# Thermistors.net
KiCad netlist of a schematic drawn in Altium Designer
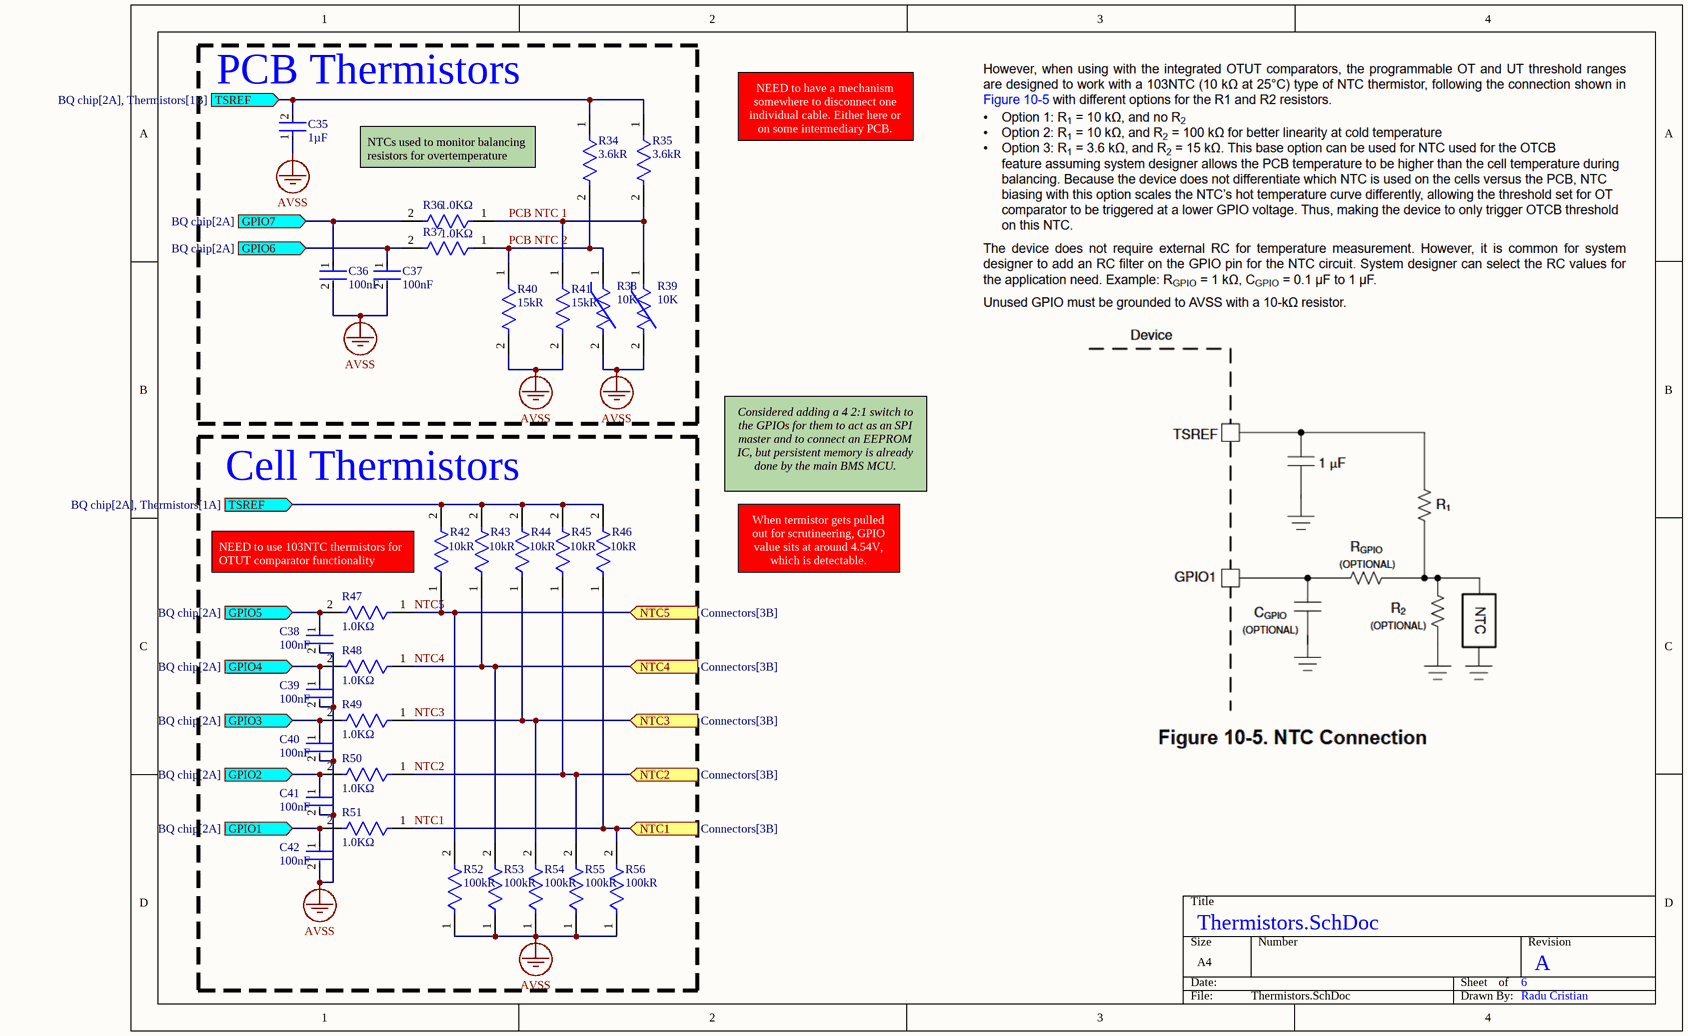
[diagram p0: Thermistors.SchDoc]

(export (version "E")
  (design (tool "Eeschema 10.0.6"))
  (components
    (comp (ref "C35")
      (value "VJ0603Y105KXJCW1BC")
      (footprint "FP-VJ0603Y105KXJCW1BC-MFG")
      (description "VJ0603Y105KXJCW1BC Multilayer Ceramic Capacitor, 1 uF, 16 V, ± 10%, X7R, 0603 [1608 Metric]")
      (fields (field (name "CAPACITANCE") "1µF") (field (name "TOLERANCE") "10%"))
      (libsource (lib "Altium Content Vault") (part "b4654b650e69147ec39a6b967a45e02"))
    )
    (comp (ref "C36")
      (value "GRM188R72A104MA35D")
      (footprint "FP-GRM188-0_1-e0_2_0_5-MFG")
      (description "Chip Multilayer Ceramic Capacitors for General Purpose, 0603, 0.10uF, X7R, 15%, 20%, 100V")
      (fields (field (name "CAPACITANCE") "100nF") (field (name "TOLERANCE") "20%"))
      (libsource (lib "Altium Content Vault") (part "11868f565c42a9108669ba33697ecf6"))
    )
    (comp (ref "C37")
      (value "GRM188R72A104MA35D")
      (footprint "FP-GRM188-0_1-e0_2_0_5-MFG")
      (description "Chip Multilayer Ceramic Capacitors for General Purpose, 0603, 0.10uF, X7R, 15%, 20%, 100V")
      (fields (field (name "CAPACITANCE") "100nF") (field (name "TOLERANCE") "20%"))
      (libsource (lib "Altium Content Vault") (part "11868f565c42a9108669ba33697ecf6"))
    )
    (comp (ref "C38")
      (value "GRM188R72A104MA35D")
      (footprint "FP-GRM188-0_1-e0_2_0_5-MFG")
      (description "Chip Multilayer Ceramic Capacitors for General Purpose, 0603, 0.10uF, X7R, 15%, 20%, 100V")
      (fields (field (name "CAPACITANCE") "100nF") (field (name "TOLERANCE") "20%"))
      (libsource (lib "Altium Content Vault") (part "11868f565c42a9108669ba33697ecf6"))
    )
    (comp (ref "C39")
      (value "GRM188R72A104MA35D")
      (footprint "FP-GRM188-0_1-e0_2_0_5-MFG")
      (description "Chip Multilayer Ceramic Capacitors for General Purpose, 0603, 0.10uF, X7R, 15%, 20%, 100V")
      (fields (field (name "CAPACITANCE") "100nF") (field (name "TOLERANCE") "20%"))
      (libsource (lib "Altium Content Vault") (part "11868f565c42a9108669ba33697ecf6"))
    )
    (comp (ref "C40")
      (value "GRM188R72A104MA35D")
      (footprint "FP-GRM188-0_1-e0_2_0_5-MFG")
      (description "Chip Multilayer Ceramic Capacitors for General Purpose, 0603, 0.10uF, X7R, 15%, 20%, 100V")
      (fields (field (name "CAPACITANCE") "100nF") (field (name "TOLERANCE") "20%"))
      (libsource (lib "Altium Content Vault") (part "11868f565c42a9108669ba33697ecf6"))
    )
    (comp (ref "C41")
      (value "GRM188R72A104MA35D")
      (footprint "FP-GRM188-0_1-e0_2_0_5-MFG")
      (description "Chip Multilayer Ceramic Capacitors for General Purpose, 0603, 0.10uF, X7R, 15%, 20%, 100V")
      (fields (field (name "CAPACITANCE") "100nF") (field (name "TOLERANCE") "20%"))
      (libsource (lib "Altium Content Vault") (part "11868f565c42a9108669ba33697ecf6"))
    )
    (comp (ref "C42")
      (value "GRM188R72A104MA35D")
      (footprint "FP-GRM188-0_1-e0_2_0_5-MFG")
      (description "Chip Multilayer Ceramic Capacitors for General Purpose, 0603, 0.10uF, X7R, 15%, 20%, 100V")
      (fields (field (name "CAPACITANCE") "100nF") (field (name "TOLERANCE") "20%"))
      (libsource (lib "Altium Content Vault") (part "11868f565c42a9108669ba33697ecf6"))
    )
    (comp (ref "R34")
      (value "AF0603FR-073K6L")
      (footprint "FP-AF0603-IPC_B")
      (description "Anti-Sulfurated Chip Resistors Automotive Grade 3.6kΩ 1% 100ppm/°C 0603")
      (fields (field (name "RESISTANCE") "3.6kR") (field (name "TOLERANCE") "1%"))
      (libsource (lib "Altium Content Vault") (part "1029c3af85768c4190bb7ad29bc67b5"))
    )
    (comp (ref "R35")
      (value "AF0603FR-073K6L")
      (footprint "FP-AF0603-IPC_B")
      (description "Anti-Sulfurated Chip Resistors Automotive Grade 3.6kΩ 1% 100ppm/°C 0603")
      (fields (field (name "RESISTANCE") "3.6kR") (field (name "TOLERANCE") "1%"))
      (libsource (lib "Altium Content Vault") (part "1029c3af85768c4190bb7ad29bc67b5"))
    )
    (comp (ref "R36")
      (value "CPF0603F1K0C1")
      (footprint "FP-CPF0603-MFG")
      (description "RES SMD 1.0KΩ 1% 1/16W 0603")
      (fields
        (field (name "OCTOPART") "https://octopart.com/cpf0603f1k0c1-te+connectivity-42013134")
        (field (name "TOLERANCE") "1%")
        (field (name "RESISTANCE") "1.0KΩ")
      )
      (libsource (lib "Altium Content Vault") (part "1029c3af85768c4190bb7ad29bc67b5"))
    )
    (comp (ref "R37")
      (value "CPF0603F1K0C1")
      (footprint "FP-CPF0603-MFG")
      (description "RES SMD 1.0KΩ 1% 1/16W 0603")
      (fields
        (field (name "OCTOPART") "https://octopart.com/cpf0603f1k0c1-te+connectivity-42013134")
        (field (name "TOLERANCE") "1%")
        (field (name "RESISTANCE") "1.0KΩ")
      )
      (libsource (lib "Altium Content Vault") (part "1029c3af85768c4190bb7ad29bc67b5"))
    )
    (comp (ref "R38")
      (value "NCG18XH103F0SRB")
      (footprint "FP-NC_18-0_15-IPC_B")
      (description "NTC Thermistor 10kΩ 1% SMD  0201 (0603 Metric)")
      (fields (field (name "TOLERANCE") "1%") (field (name "PARAMETER 1") "10K"))
      (libsource (lib "Altium Content Vault") (part "3b148a6ebabc5fb4d708a66c052d352"))
    )
    (comp (ref "R39")
      (value "NCG18XH103F0SRB")
      (footprint "FP-NC_18-0_15-IPC_B")
      (description "NTC Thermistor 10kΩ 1% SMD  0201 (0603 Metric)")
      (fields (field (name "TOLERANCE") "1%") (field (name "PARAMETER 1") "10K"))
      (libsource (lib "Altium Content Vault") (part "3b148a6ebabc5fb4d708a66c052d352"))
    )
    (comp (ref "R40")
      (value "RNCP0603FTD15K0")
      (footprint "FP-RNCP0603-IPC_C")
      (description "15kΩ ±1% 0.125W 0603 High Power Anti-Sulfur Thin Film Chip Resistor")
      (fields (field (name "TOLERANCE") "1%") (field (name "RESISTANCE") "15kR"))
      (libsource (lib "Altium Content Vault") (part "1029c3af85768c4190bb7ad29bc67b5"))
    )
    (comp (ref "R41")
      (value "RNCP0603FTD15K0")
      (footprint "FP-RNCP0603-IPC_C")
      (description "15kΩ ±1% 0.125W 0603 High Power Anti-Sulfur Thin Film Chip Resistor")
      (fields (field (name "TOLERANCE") "1%") (field (name "RESISTANCE") "15kR"))
      (libsource (lib "Altium Content Vault") (part "1029c3af85768c4190bb7ad29bc67b5"))
    )
    (comp (ref "R42")
      (value "MCT0603MC1002FP500")
      (footprint "FP-MCT0603-IPC_C")
      (description "RES SMD 100 OHM 1% 1/8W 0603")
      (fields (field (name "TOLERANCE") "1%") (field (name "RESISTANCE") "10kR"))
      (libsource (lib "Altium Content Vault") (part "1029c3af85768c4190bb7ad29bc67b5"))
    )
    (comp (ref "R43")
      (value "MCT0603MC1002FP500")
      (footprint "FP-MCT0603-IPC_C")
      (description "RES SMD 100 OHM 1% 1/8W 0603")
      (fields (field (name "TOLERANCE") "1%") (field (name "RESISTANCE") "10kR"))
      (libsource (lib "Altium Content Vault") (part "1029c3af85768c4190bb7ad29bc67b5"))
    )
    (comp (ref "R44")
      (value "MCT0603MC1002FP500")
      (footprint "FP-MCT0603-IPC_C")
      (description "RES SMD 100 OHM 1% 1/8W 0603")
      (fields (field (name "TOLERANCE") "1%") (field (name "RESISTANCE") "10kR"))
      (libsource (lib "Altium Content Vault") (part "1029c3af85768c4190bb7ad29bc67b5"))
    )
    (comp (ref "R45")
      (value "MCT0603MC1002FP500")
      (footprint "FP-MCT0603-IPC_C")
      (description "RES SMD 100 OHM 1% 1/8W 0603")
      (fields (field (name "TOLERANCE") "1%") (field (name "RESISTANCE") "10kR"))
      (libsource (lib "Altium Content Vault") (part "1029c3af85768c4190bb7ad29bc67b5"))
    )
    (comp (ref "R46")
      (value "MCT0603MC1002FP500")
      (footprint "FP-MCT0603-IPC_C")
      (description "RES SMD 100 OHM 1% 1/8W 0603")
      (fields (field (name "TOLERANCE") "1%") (field (name "RESISTANCE") "10kR"))
      (libsource (lib "Altium Content Vault") (part "1029c3af85768c4190bb7ad29bc67b5"))
    )
    (comp (ref "R47")
      (value "CPF0603F1K0C1")
      (footprint "FP-CPF0603-IPC_C")
      (description "RES SMD 1.0KΩ 1% 1/16W 0603")
      (fields
        (field (name "OCTOPART") "https://octopart.com/cpf0603f1k0c1-te+connectivity-42013134")
        (field (name "TOLERANCE") "1%")
        (field (name "RESISTANCE") "1.0KΩ")
      )
      (libsource (lib "Altium Content Vault") (part "1029c3af85768c4190bb7ad29bc67b5"))
    )
    (comp (ref "R48")
      (value "CPF0603F1K0C1")
      (footprint "FP-CPF0603-IPC_C")
      (description "RES SMD 1.0KΩ 1% 1/16W 0603")
      (fields
        (field (name "OCTOPART") "https://octopart.com/cpf0603f1k0c1-te+connectivity-42013134")
        (field (name "TOLERANCE") "1%")
        (field (name "RESISTANCE") "1.0KΩ")
      )
      (libsource (lib "Altium Content Vault") (part "1029c3af85768c4190bb7ad29bc67b5"))
    )
    (comp (ref "R49")
      (value "CPF0603F1K0C1")
      (footprint "FP-CPF0603-IPC_C")
      (description "RES SMD 1.0KΩ 1% 1/16W 0603")
      (fields
        (field (name "OCTOPART") "https://octopart.com/cpf0603f1k0c1-te+connectivity-42013134")
        (field (name "TOLERANCE") "1%")
        (field (name "RESISTANCE") "1.0KΩ")
      )
      (libsource (lib "Altium Content Vault") (part "1029c3af85768c4190bb7ad29bc67b5"))
    )
    (comp (ref "R50")
      (value "CPF0603F1K0C1")
      (footprint "FP-CPF0603-IPC_C")
      (description "RES SMD 1.0KΩ 1% 1/16W 0603")
      (fields
        (field (name "OCTOPART") "https://octopart.com/cpf0603f1k0c1-te+connectivity-42013134")
        (field (name "TOLERANCE") "1%")
        (field (name "RESISTANCE") "1.0KΩ")
      )
      (libsource (lib "Altium Content Vault") (part "1029c3af85768c4190bb7ad29bc67b5"))
    )
    (comp (ref "R51")
      (value "CPF0603F1K0C1")
      (footprint "FP-CPF0603-IPC_C")
      (description "RES SMD 1.0KΩ 1% 1/16W 0603")
      (fields
        (field (name "OCTOPART") "https://octopart.com/cpf0603f1k0c1-te+connectivity-42013134")
        (field (name "TOLERANCE") "1%")
        (field (name "RESISTANCE") "1.0KΩ")
      )
      (libsource (lib "Altium Content Vault") (part "1029c3af85768c4190bb7ad29bc67b5"))
    )
    (comp (ref "R52")
      (value "MCT0603MC1003FP500")
      (footprint "FP-MCT0603-IPC_C")
      (description "RES SMD 100 OHM 1% 1/8W 0603")
      (fields (field (name "TOLERANCE") "1%") (field (name "RESISTANCE") "100kR"))
      (libsource (lib "Altium Content Vault") (part "1029c3af85768c4190bb7ad29bc67b5"))
    )
    (comp (ref "R53")
      (value "MCT0603MC1003FP500")
      (footprint "FP-MCT0603-IPC_C")
      (description "RES SMD 100 OHM 1% 1/8W 0603")
      (fields (field (name "TOLERANCE") "1%") (field (name "RESISTANCE") "100kR"))
      (libsource (lib "Altium Content Vault") (part "1029c3af85768c4190bb7ad29bc67b5"))
    )
    (comp (ref "R54")
      (value "MCT0603MC1003FP500")
      (footprint "FP-MCT0603-IPC_C")
      (description "RES SMD 100 OHM 1% 1/8W 0603")
      (fields (field (name "TOLERANCE") "1%") (field (name "RESISTANCE") "100kR"))
      (libsource (lib "Altium Content Vault") (part "1029c3af85768c4190bb7ad29bc67b5"))
    )
    (comp (ref "R55")
      (value "MCT0603MC1003FP500")
      (footprint "FP-MCT0603-IPC_C")
      (description "RES SMD 100 OHM 1% 1/8W 0603")
      (fields (field (name "TOLERANCE") "1%") (field (name "RESISTANCE") "100kR"))
      (libsource (lib "Altium Content Vault") (part "1029c3af85768c4190bb7ad29bc67b5"))
    )
    (comp (ref "R56")
      (value "MCT0603MC1003FP500")
      (footprint "FP-MCT0603-IPC_C")
      (description "RES SMD 100 OHM 1% 1/8W 0603")
      (fields (field (name "TOLERANCE") "1%") (field (name "RESISTANCE") "100kR"))
      (libsource (lib "Altium Content Vault") (part "1029c3af85768c4190bb7ad29bc67b5"))
    )
  )
  (nets
    (net (code "1") (name "/GPIO1") (class "Default")
      (node (ref "C42") (pin "1") (pinfunction "1_1") (pintype "passive"))
      (node (ref "R51") (pin "2") (pinfunction "2_2") (pintype "passive"))
    )
    (net (code "2") (name "/GPIO2") (class "Default")
      (node (ref "C41") (pin "1") (pinfunction "1_1") (pintype "passive"))
      (node (ref "R50") (pin "2") (pinfunction "2_2") (pintype "passive"))
    )
    (net (code "3") (name "/GPIO3") (class "Default")
      (node (ref "C40") (pin "1") (pinfunction "1_1") (pintype "passive"))
      (node (ref "R49") (pin "2") (pinfunction "2_2") (pintype "passive"))
    )
    (net (code "4") (name "/GPIO4") (class "Default")
      (node (ref "C39") (pin "1") (pinfunction "1_1") (pintype "passive"))
      (node (ref "R48") (pin "2") (pinfunction "2_2") (pintype "passive"))
    )
    (net (code "5") (name "/GPIO5") (class "Default")
      (node (ref "C38") (pin "1") (pinfunction "1_1") (pintype "passive"))
      (node (ref "R47") (pin "2") (pinfunction "2_2") (pintype "passive"))
    )
    (net (code "6") (name "/GPIO6") (class "Default")
      (node (ref "C37") (pin "1") (pinfunction "1_1") (pintype "passive"))
      (node (ref "R37") (pin "2") (pinfunction "2_2") (pintype "passive"))
    )
    (net (code "7") (name "/GPIO7") (class "Default")
      (node (ref "C36") (pin "1") (pinfunction "1_1") (pintype "passive"))
      (node (ref "R36") (pin "2") (pinfunction "2_2") (pintype "passive"))
    )
    (net (code "8") (name "/NTC1") (class "Default")
      (node (ref "R46") (pin "1") (pinfunction "1_1") (pintype "passive"))
      (node (ref "R51") (pin "1") (pinfunction "1_1") (pintype "passive"))
      (node (ref "R56") (pin "2") (pinfunction "2_2") (pintype "passive"))
    )
    (net (code "9") (name "/NTC2") (class "Default")
      (node (ref "R45") (pin "1") (pinfunction "1_1") (pintype "passive"))
      (node (ref "R50") (pin "1") (pinfunction "1_1") (pintype "passive"))
      (node (ref "R55") (pin "2") (pinfunction "2_2") (pintype "passive"))
    )
    (net (code "10") (name "/NTC3") (class "Default")
      (node (ref "R44") (pin "1") (pinfunction "1_1") (pintype "passive"))
      (node (ref "R49") (pin "1") (pinfunction "1_1") (pintype "passive"))
      (node (ref "R54") (pin "2") (pinfunction "2_2") (pintype "passive"))
    )
    (net (code "11") (name "/NTC4") (class "Default")
      (node (ref "R43") (pin "1") (pinfunction "1_1") (pintype "passive"))
      (node (ref "R48") (pin "1") (pinfunction "1_1") (pintype "passive"))
      (node (ref "R53") (pin "2") (pinfunction "2_2") (pintype "passive"))
    )
    (net (code "12") (name "/NTC5") (class "Default")
      (node (ref "R42") (pin "1") (pinfunction "1_1") (pintype "passive"))
      (node (ref "R47") (pin "1") (pinfunction "1_1") (pintype "passive"))
      (node (ref "R52") (pin "2") (pinfunction "2_2") (pintype "passive"))
    )
    (net (code "13") (name "/PCB NTC 1") (class "Default")
      (node (ref "R35") (pin "2") (pinfunction "2_2") (pintype "passive"))
      (node (ref "R36") (pin "1") (pinfunction "1_1") (pintype "passive"))
      (node (ref "R39") (pin "1") (pinfunction "1_1") (pintype "passive"))
      (node (ref "R41") (pin "1") (pinfunction "1_1") (pintype "passive"))
    )
    (net (code "14") (name "/PCB NTC 2") (class "Default")
      (node (ref "R34") (pin "2") (pinfunction "2_2") (pintype "passive"))
      (node (ref "R37") (pin "1") (pinfunction "1_1") (pintype "passive"))
      (node (ref "R38") (pin "1") (pinfunction "1_1") (pintype "passive"))
      (node (ref "R40") (pin "1") (pinfunction "1_1") (pintype "passive"))
    )
    (net (code "15") (name "/TSREF") (class "Default")
      (node (ref "C35") (pin "2") (pinfunction "2_2") (pintype "passive"))
      (node (ref "R34") (pin "1") (pinfunction "1_1") (pintype "passive"))
      (node (ref "R35") (pin "1") (pinfunction "1_1") (pintype "passive"))
      (node (ref "R42") (pin "2") (pinfunction "2_2") (pintype "passive"))
      (node (ref "R43") (pin "2") (pinfunction "2_2") (pintype "passive"))
      (node (ref "R44") (pin "2") (pinfunction "2_2") (pintype "passive"))
      (node (ref "R45") (pin "2") (pinfunction "2_2") (pintype "passive"))
      (node (ref "R46") (pin "2") (pinfunction "2_2") (pintype "passive"))
    )
    (net (code "16") (name "AVSS") (class "Default")
      (node (ref "C35") (pin "1") (pinfunction "1_1") (pintype "passive"))
      (node (ref "C36") (pin "2") (pinfunction "2_2") (pintype "passive"))
      (node (ref "C37") (pin "2") (pinfunction "2_2") (pintype "passive"))
      (node (ref "C38") (pin "2") (pinfunction "2_2") (pintype "passive"))
      (node (ref "C39") (pin "2") (pinfunction "2_2") (pintype "passive"))
      (node (ref "C40") (pin "2") (pinfunction "2_2") (pintype "passive"))
      (node (ref "C41") (pin "2") (pinfunction "2_2") (pintype "passive"))
      (node (ref "C42") (pin "2") (pinfunction "2_2") (pintype "passive"))
      (node (ref "R38") (pin "2") (pinfunction "2_2") (pintype "passive"))
      (node (ref "R39") (pin "2") (pinfunction "2_2") (pintype "passive"))
      (node (ref "R40") (pin "2") (pinfunction "2_2") (pintype "passive"))
      (node (ref "R41") (pin "2") (pinfunction "2_2") (pintype "passive"))
      (node (ref "R52") (pin "1") (pinfunction "1_1") (pintype "passive"))
      (node (ref "R53") (pin "1") (pinfunction "1_1") (pintype "passive"))
      (node (ref "R54") (pin "1") (pinfunction "1_1") (pintype "passive"))
      (node (ref "R55") (pin "1") (pinfunction "1_1") (pintype "passive"))
      (node (ref "R56") (pin "1") (pinfunction "1_1") (pintype "passive"))
    )
  )
)
